# smartsensor_jig.net
KiCad netlist of a schematic drawn in EAGLE
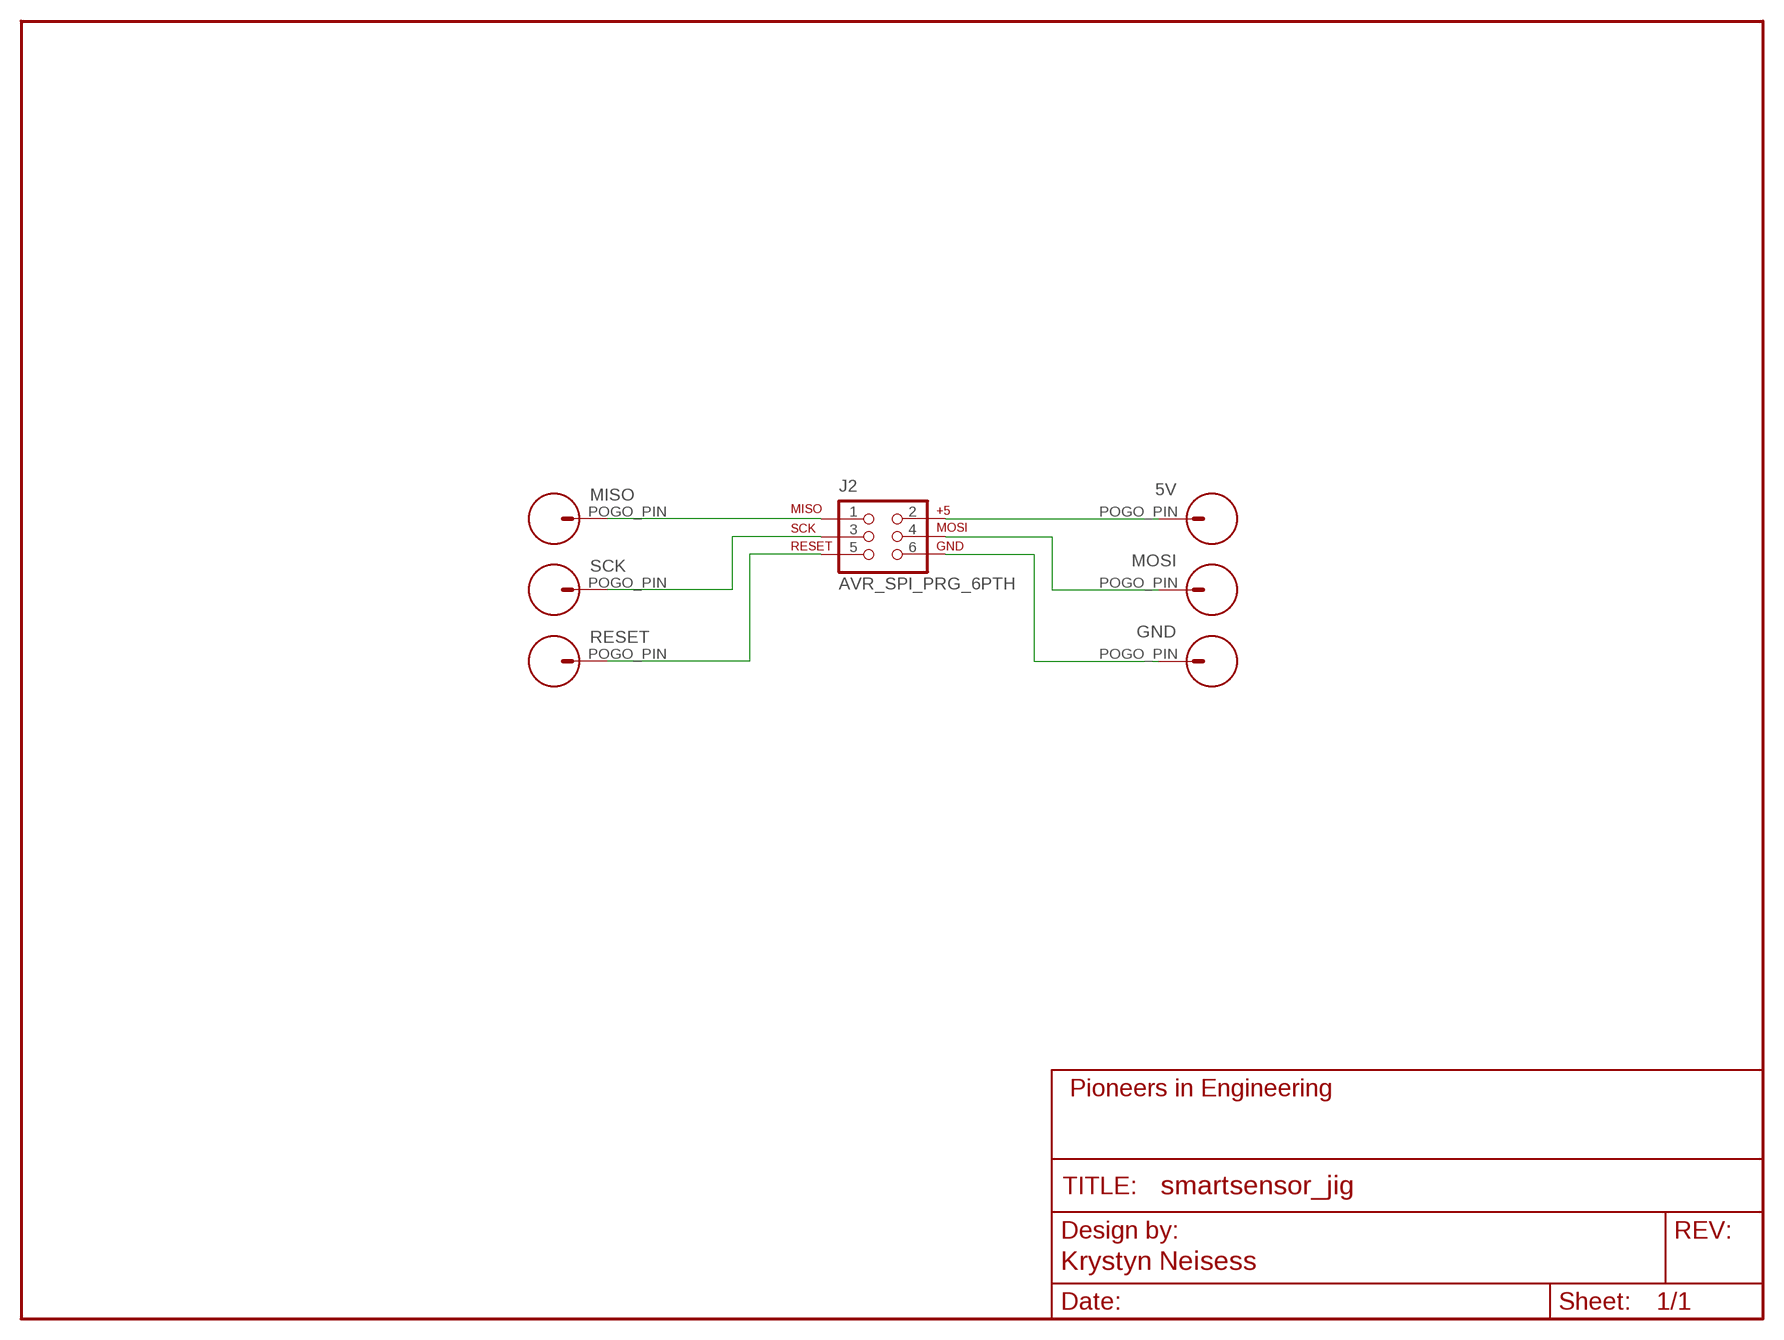
[diagram p0: schematic, sheet 1]

(export (version "E")
  (design (tool "Eeschema 10.0.6"))
  (components
    (comp (ref "5V")
      (value "POGO_PIN")
      (footprint "eagle-import:POGO_PIN_394")
      (libsource (lib "eagle-import") (part "POGO_PIN"))
    )
    (comp (ref "GND")
      (value "POGO_PIN")
      (footprint "eagle-import:POGO_PIN_394")
      (libsource (lib "eagle-import") (part "POGO_PIN"))
    )
    (comp (ref "J2")
      (value "AVR_SPI_PRG_6PTH")
      (footprint "eagle-import:2X3")
      (libsource (lib "eagle-import") (part "AVR_SPI_PRG_6PTH"))
    )
    (comp (ref "MISO")
      (value "POGO_PIN")
      (footprint "eagle-import:POGO_PIN_394")
      (libsource (lib "eagle-import") (part "POGO_PIN"))
    )
    (comp (ref "MOSI")
      (value "POGO_PIN")
      (footprint "eagle-import:POGO_PIN_394")
      (libsource (lib "eagle-import") (part "POGO_PIN"))
    )
    (comp (ref "RESET")
      (value "POGO_PIN")
      (footprint "eagle-import:POGO_PIN_394")
      (libsource (lib "eagle-import") (part "POGO_PIN"))
    )
    (comp (ref "SCK")
      (value "POGO_PIN")
      (footprint "eagle-import:POGO_PIN_394")
      (libsource (lib "eagle-import") (part "POGO_PIN"))
    )
  )
  (nets
    (net (code "1") (name "Net-(5V-P$1)") (class "Default")
      (node (ref "5V") (pin "POGO_PIN") (pinfunction "P$1_POGO_PIN") (pintype "bidirectional"))
      (node (ref "J2") (pin "2") (pinfunction "2_2") (pintype "passive"))
    )
    (net (code "2") (name "Net-(GND-P$1)") (class "Default")
      (node (ref "GND") (pin "POGO_PIN") (pinfunction "P$1_POGO_PIN") (pintype "bidirectional"))
      (node (ref "J2") (pin "6") (pinfunction "6_6") (pintype "passive"))
    )
    (net (code "3") (name "Net-(MISO-P$1)") (class "Default")
      (node (ref "J2") (pin "1") (pinfunction "1_1") (pintype "passive"))
      (node (ref "MISO") (pin "POGO_PIN") (pinfunction "P$1_POGO_PIN") (pintype "bidirectional"))
    )
    (net (code "4") (name "Net-(MOSI-P$1)") (class "Default")
      (node (ref "J2") (pin "4") (pinfunction "4_4") (pintype "passive"))
      (node (ref "MOSI") (pin "POGO_PIN") (pinfunction "P$1_POGO_PIN") (pintype "bidirectional"))
    )
    (net (code "5") (name "Net-(RESET-P$1)") (class "Default")
      (node (ref "J2") (pin "5") (pinfunction "5_5") (pintype "passive"))
      (node (ref "RESET") (pin "POGO_PIN") (pinfunction "P$1_POGO_PIN") (pintype "bidirectional"))
    )
    (net (code "6") (name "Net-(SCK-P$1)") (class "Default")
      (node (ref "J2") (pin "3") (pinfunction "3_3") (pintype "passive"))
      (node (ref "SCK") (pin "POGO_PIN") (pinfunction "P$1_POGO_PIN") (pintype "bidirectional"))
    )
  )
)
